# schema_zasuvka.net
KiCad netlist of a schematic drawn in EAGLE
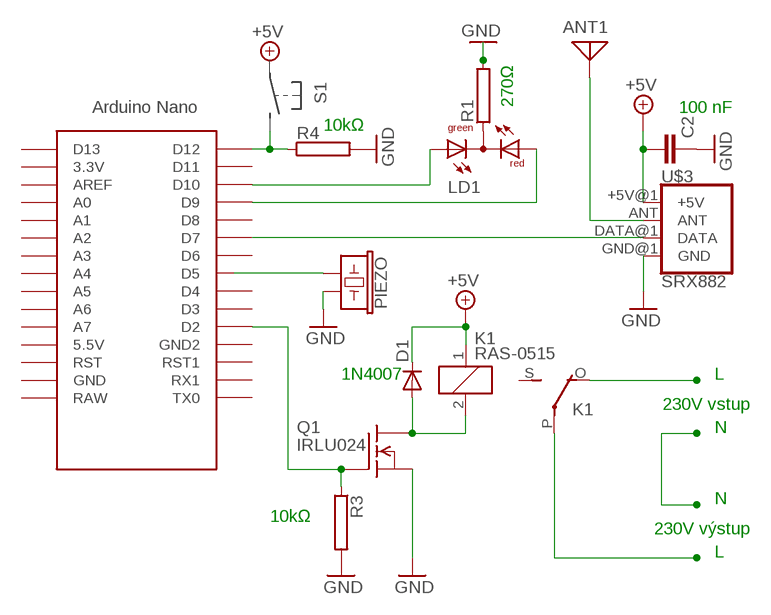
[diagram p0: schematic, sheet 1]

(export (version "E")
  (design (tool "Eeschema 10.0.6"))
  (components
    (comp (ref "ANT1")
      (value "ANTENNA")
      (footprint "eagle-import:PAD-01")
      (libsource (lib "eagle-import") (part "ANTENNA"))
    )
    (comp (ref "C2")
      (value "C5/5.5")
      (footprint "eagle-import:C5B5.5")
      (libsource (lib "eagle-import") (part "C5/5.5"))
    )
    (comp (ref "D1")
      (value "1N4004")
      (footprint "eagle-import:DO41-10")
      (libsource (lib "eagle-import") (part "1N4004"))
    )
    (comp (ref "K1")
      (value "RAS-0515")
      (footprint "eagle-import:G5LE")
      (libsource (lib "eagle-import") (part "G5L"))
    )
    (comp (ref "LD1")
      (value "DUOLED-RG-C")
      (footprint "eagle-import:DUOLED-C-5MM")
      (libsource (lib "eagle-import") (part "DUOLED-RG-C"))
    )
    (comp (ref "PIEZO")
      (value "BUZZER-PTH_KIT")
      (footprint "eagle-import:BUZZER-12MM-KIT")
      (libsource (lib "eagle-import") (part "BUZZER-PTH_KIT"))
    )
    (comp (ref "Q1")
      (value "IRLU024")
      (footprint "eagle-import:TO220")
      (libsource (lib "eagle-import") (part "BUZ10"))
    )
    (comp (ref "R1")
      (value "RAC03")
      (footprint "eagle-import:AC03")
      (libsource (lib "eagle-import") (part "RAC03"))
    )
    (comp (ref "R3")
      (value "RAC03")
      (footprint "eagle-import:AC03")
      (libsource (lib "eagle-import") (part "RAC03"))
    )
    (comp (ref "R4")
      (value "RAC03")
      (footprint "eagle-import:AC03")
      (libsource (lib "eagle-import") (part "RAC03"))
    )
    (comp (ref "U$1")
      (value "NANO")
      (footprint "eagle-import:NANO")
      (libsource (lib "eagle-import") (part "NANO"))
    )
    (comp (ref "U$3")
      (value "SRX882")
      (footprint "eagle-import:RF-LINK_RX")
      (libsource (lib "eagle-import") (part "RF-LINK_RX"))
    )
  )
  (nets
    (net (code "1") (name "+5V") (class "Default")
      (node (ref "C2") (pin "2") (pinfunction "2_2") (pintype "passive"))
      (node (ref "D1") (pin "C") (pinfunction "C_C") (pintype "passive"))
      (node (ref "K1") (pin "1") (pinfunction "1_1") (pintype "passive"))
      (node (ref "U$3") (pin "+5V@1") (pinfunction "+5V_+5V@1") (pintype "power_in"))
    )
    (net (code "2") (name "/N$11") (class "Default")
      (node (ref "K1") (pin "P") (pinfunction "P_P") (pintype "passive"))
    )
    (net (code "3") (name "GND") (class "Default")
      (node (ref "C2") (pin "1") (pinfunction "1_1") (pintype "passive"))
      (node (ref "PIEZO") (pin "+") (pinfunction "1_+") (pintype "passive"))
      (node (ref "Q1") (pin "3") (pinfunction "S_3") (pintype "passive"))
      (node (ref "R1") (pin "2") (pinfunction "2_2") (pintype "passive"))
      (node (ref "R3") (pin "2") (pinfunction "2_2") (pintype "passive"))
      (node (ref "R4") (pin "2") (pinfunction "2_2") (pintype "passive"))
      (node (ref "U$3") (pin "GND@1") (pinfunction "GND_GND@1") (pintype "power_in"))
    )
    (net (code "4") (name "Net-(ANT1-Pad1)") (class "Default")
      (node (ref "ANT1") (pin "1") (pinfunction "1_1") (pintype "output"))
      (node (ref "U$3") (pin "ANT") (pinfunction "ANT_ANT") (pintype "passive"))
    )
    (net (code "5") (name "Net-(LD1-AG)") (class "Default")
      (node (ref "LD1") (pin "AX") (pinfunction "AG_AX") (pintype "passive"))
      (node (ref "U$1") (pin "D10") (pinfunction "D10_D10") (pintype "bidirectional"))
    )
    (net (code "6") (name "Net-(LD1-PadAR)") (class "Default")
      (node (ref "LD1") (pin "AR") (pinfunction "AR_AR") (pintype "passive"))
      (node (ref "U$1") (pin "D9") (pinfunction "D9_D9") (pintype "bidirectional"))
    )
    (net (code "7") (name "Net-(LD1-PadC)") (class "Default")
      (node (ref "LD1") (pin "C") (pinfunction "C_C") (pintype "passive"))
      (node (ref "R1") (pin "1") (pinfunction "1_1") (pintype "passive"))
    )
    (net (code "8") (name "Net-(Q1-D)") (class "Default")
      (node (ref "D1") (pin "A") (pinfunction "A_A") (pintype "passive"))
      (node (ref "K1") (pin "2") (pinfunction "2_2") (pintype "passive"))
      (node (ref "Q1") (pin "2") (pinfunction "D_2") (pintype "passive"))
    )
    (net (code "9") (name "Net-(Q1-G)") (class "Default")
      (node (ref "Q1") (pin "1") (pinfunction "G_1") (pintype "passive"))
      (node (ref "R3") (pin "1") (pinfunction "1_1") (pintype "passive"))
      (node (ref "U$1") (pin "D2") (pinfunction "D2_D2") (pintype "bidirectional"))
    )
    (net (code "10") (name "Net-(R4-Pad1)") (class "Default")
      (node (ref "R4") (pin "1") (pinfunction "1_1") (pintype "passive"))
      (node (ref "U$1") (pin "D12") (pinfunction "D12_D12") (pintype "bidirectional"))
    )
    (net (code "11") (name "Net-(U$3-DATA)") (class "Default")
      (node (ref "U$1") (pin "D7") (pinfunction "D7_D7") (pintype "bidirectional"))
      (node (ref "U$3") (pin "DATA@1") (pinfunction "DATA_DATA@1") (pintype "input"))
    )
    (net (code "12") (name "unconnected-(K1-PadO)") (class "Default")
      (node (ref "K1") (pin "O") (pinfunction "O_O") (pintype "passive"))
    )
    (net (code "13") (name "unconnected-(K1-PadS)") (class "Default")
      (node (ref "K1") (pin "S") (pinfunction "S_S") (pintype "passive"))
    )
    (net (code "14") (name "unconnected-(PIEZO-2-Pad-)") (class "Default")
      (node (ref "PIEZO") (pin "-") (pinfunction "2_-") (pintype "passive"))
    )
    (net (code "15") (name "unconnected-(U$1-5.5V-Pad5V)") (class "Default")
      (node (ref "U$1") (pin "5V") (pinfunction "5.5V_5V") (pintype "bidirectional"))
    )
    (net (code "16") (name "unconnected-(U$1-GND2-PadGND1)") (class "Default")
      (node (ref "U$1") (pin "GND1") (pinfunction "GND2_GND1") (pintype "bidirectional"))
    )
    (net (code "17") (name "unconnected-(U$1-Pad3.3V)") (class "Default")
      (node (ref "U$1") (pin "3.3V") (pinfunction "3.3V_3.3V") (pintype "bidirectional"))
    )
    (net (code "18") (name "unconnected-(U$1-PadA0)") (class "Default")
      (node (ref "U$1") (pin "A0") (pinfunction "A0_A0") (pintype "bidirectional"))
    )
    (net (code "19") (name "unconnected-(U$1-PadA1)") (class "Default")
      (node (ref "U$1") (pin "A1") (pinfunction "A1_A1") (pintype "bidirectional"))
    )
    (net (code "20") (name "unconnected-(U$1-PadA2)") (class "Default")
      (node (ref "U$1") (pin "A2") (pinfunction "A2_A2") (pintype "bidirectional"))
    )
    (net (code "21") (name "unconnected-(U$1-PadA3)") (class "Default")
      (node (ref "U$1") (pin "A3") (pinfunction "A3_A3") (pintype "bidirectional"))
    )
    (net (code "22") (name "unconnected-(U$1-PadA4)") (class "Default")
      (node (ref "U$1") (pin "A4") (pinfunction "A4_A4") (pintype "bidirectional"))
    )
    (net (code "23") (name "unconnected-(U$1-PadA5)") (class "Default")
      (node (ref "U$1") (pin "A5") (pinfunction "A5_A5") (pintype "bidirectional"))
    )
    (net (code "24") (name "unconnected-(U$1-PadA6)") (class "Default")
      (node (ref "U$1") (pin "A6") (pinfunction "A6_A6") (pintype "bidirectional"))
    )
    (net (code "25") (name "unconnected-(U$1-PadA7)") (class "Default")
      (node (ref "U$1") (pin "A7") (pinfunction "A7_A7") (pintype "bidirectional"))
    )
    (net (code "26") (name "unconnected-(U$1-PadAREF)") (class "Default")
      (node (ref "U$1") (pin "AREF") (pinfunction "AREF_AREF") (pintype "bidirectional"))
    )
    (net (code "27") (name "unconnected-(U$1-PadD3)") (class "Default")
      (node (ref "U$1") (pin "D3") (pinfunction "D3_D3") (pintype "bidirectional"))
    )
    (net (code "28") (name "unconnected-(U$1-PadD4)") (class "Default")
      (node (ref "U$1") (pin "D4") (pinfunction "D4_D4") (pintype "bidirectional"))
    )
    (net (code "29") (name "unconnected-(U$1-PadD5)") (class "Default")
      (node (ref "U$1") (pin "D5") (pinfunction "D5_D5") (pintype "bidirectional"))
    )
    (net (code "30") (name "unconnected-(U$1-PadD6)") (class "Default")
      (node (ref "U$1") (pin "D6") (pinfunction "D6_D6") (pintype "bidirectional"))
    )
    (net (code "31") (name "unconnected-(U$1-PadD8)") (class "Default")
      (node (ref "U$1") (pin "D8") (pinfunction "D8_D8") (pintype "bidirectional"))
    )
    (net (code "32") (name "unconnected-(U$1-PadD11)") (class "Default")
      (node (ref "U$1") (pin "D11") (pinfunction "D11_D11") (pintype "bidirectional"))
    )
    (net (code "33") (name "unconnected-(U$1-PadD13)") (class "Default")
      (node (ref "U$1") (pin "D13") (pinfunction "D13_D13") (pintype "bidirectional"))
    )
    (net (code "34") (name "unconnected-(U$1-PadGND)") (class "Default")
      (node (ref "U$1") (pin "GND") (pinfunction "GND_GND") (pintype "bidirectional"))
    )
    (net (code "35") (name "unconnected-(U$1-PadICSP1)") (class "Default")
      (node (ref "U$1") (pin "ICSP1") (pinfunction "ICSP1_ICSP1") (pintype "bidirectional"))
    )
    (net (code "36") (name "unconnected-(U$1-PadICSP2)") (class "Default")
      (node (ref "U$1") (pin "ICSP2") (pinfunction "ICSP2_ICSP2") (pintype "bidirectional"))
    )
    (net (code "37") (name "unconnected-(U$1-PadICSP3)") (class "Default")
      (node (ref "U$1") (pin "ICSP3") (pinfunction "ICSP3_ICSP3") (pintype "bidirectional"))
    )
    (net (code "38") (name "unconnected-(U$1-PadICSP4)") (class "Default")
      (node (ref "U$1") (pin "ICSP4") (pinfunction "ICSP4_ICSP4") (pintype "bidirectional"))
    )
    (net (code "39") (name "unconnected-(U$1-PadICSP5)") (class "Default")
      (node (ref "U$1") (pin "ICSP5") (pinfunction "ICSP5_ICSP5") (pintype "bidirectional"))
    )
    (net (code "40") (name "unconnected-(U$1-PadICSP6)") (class "Default")
      (node (ref "U$1") (pin "ICSP6") (pinfunction "ICSP6_ICSP6") (pintype "bidirectional"))
    )
    (net (code "41") (name "unconnected-(U$1-PadRAW)") (class "Default")
      (node (ref "U$1") (pin "RAW") (pinfunction "RAW_RAW") (pintype "bidirectional"))
    )
    (net (code "42") (name "unconnected-(U$1-PadRST)") (class "Default")
      (node (ref "U$1") (pin "RST") (pinfunction "RST_RST") (pintype "bidirectional"))
    )
    (net (code "43") (name "unconnected-(U$1-PadRST1)") (class "Default")
      (node (ref "U$1") (pin "RST1") (pinfunction "RST1_RST1") (pintype "bidirectional"))
    )
    (net (code "44") (name "unconnected-(U$1-PadRX1)") (class "Default")
      (node (ref "U$1") (pin "RX1") (pinfunction "RX1_RX1") (pintype "bidirectional"))
    )
    (net (code "45") (name "unconnected-(U$1-PadTX0)") (class "Default")
      (node (ref "U$1") (pin "TX0") (pinfunction "TX0_TX0") (pintype "bidirectional"))
    )
  )
)
